# Connector.net
KiCad netlist of a schematic drawn in Altium Designer
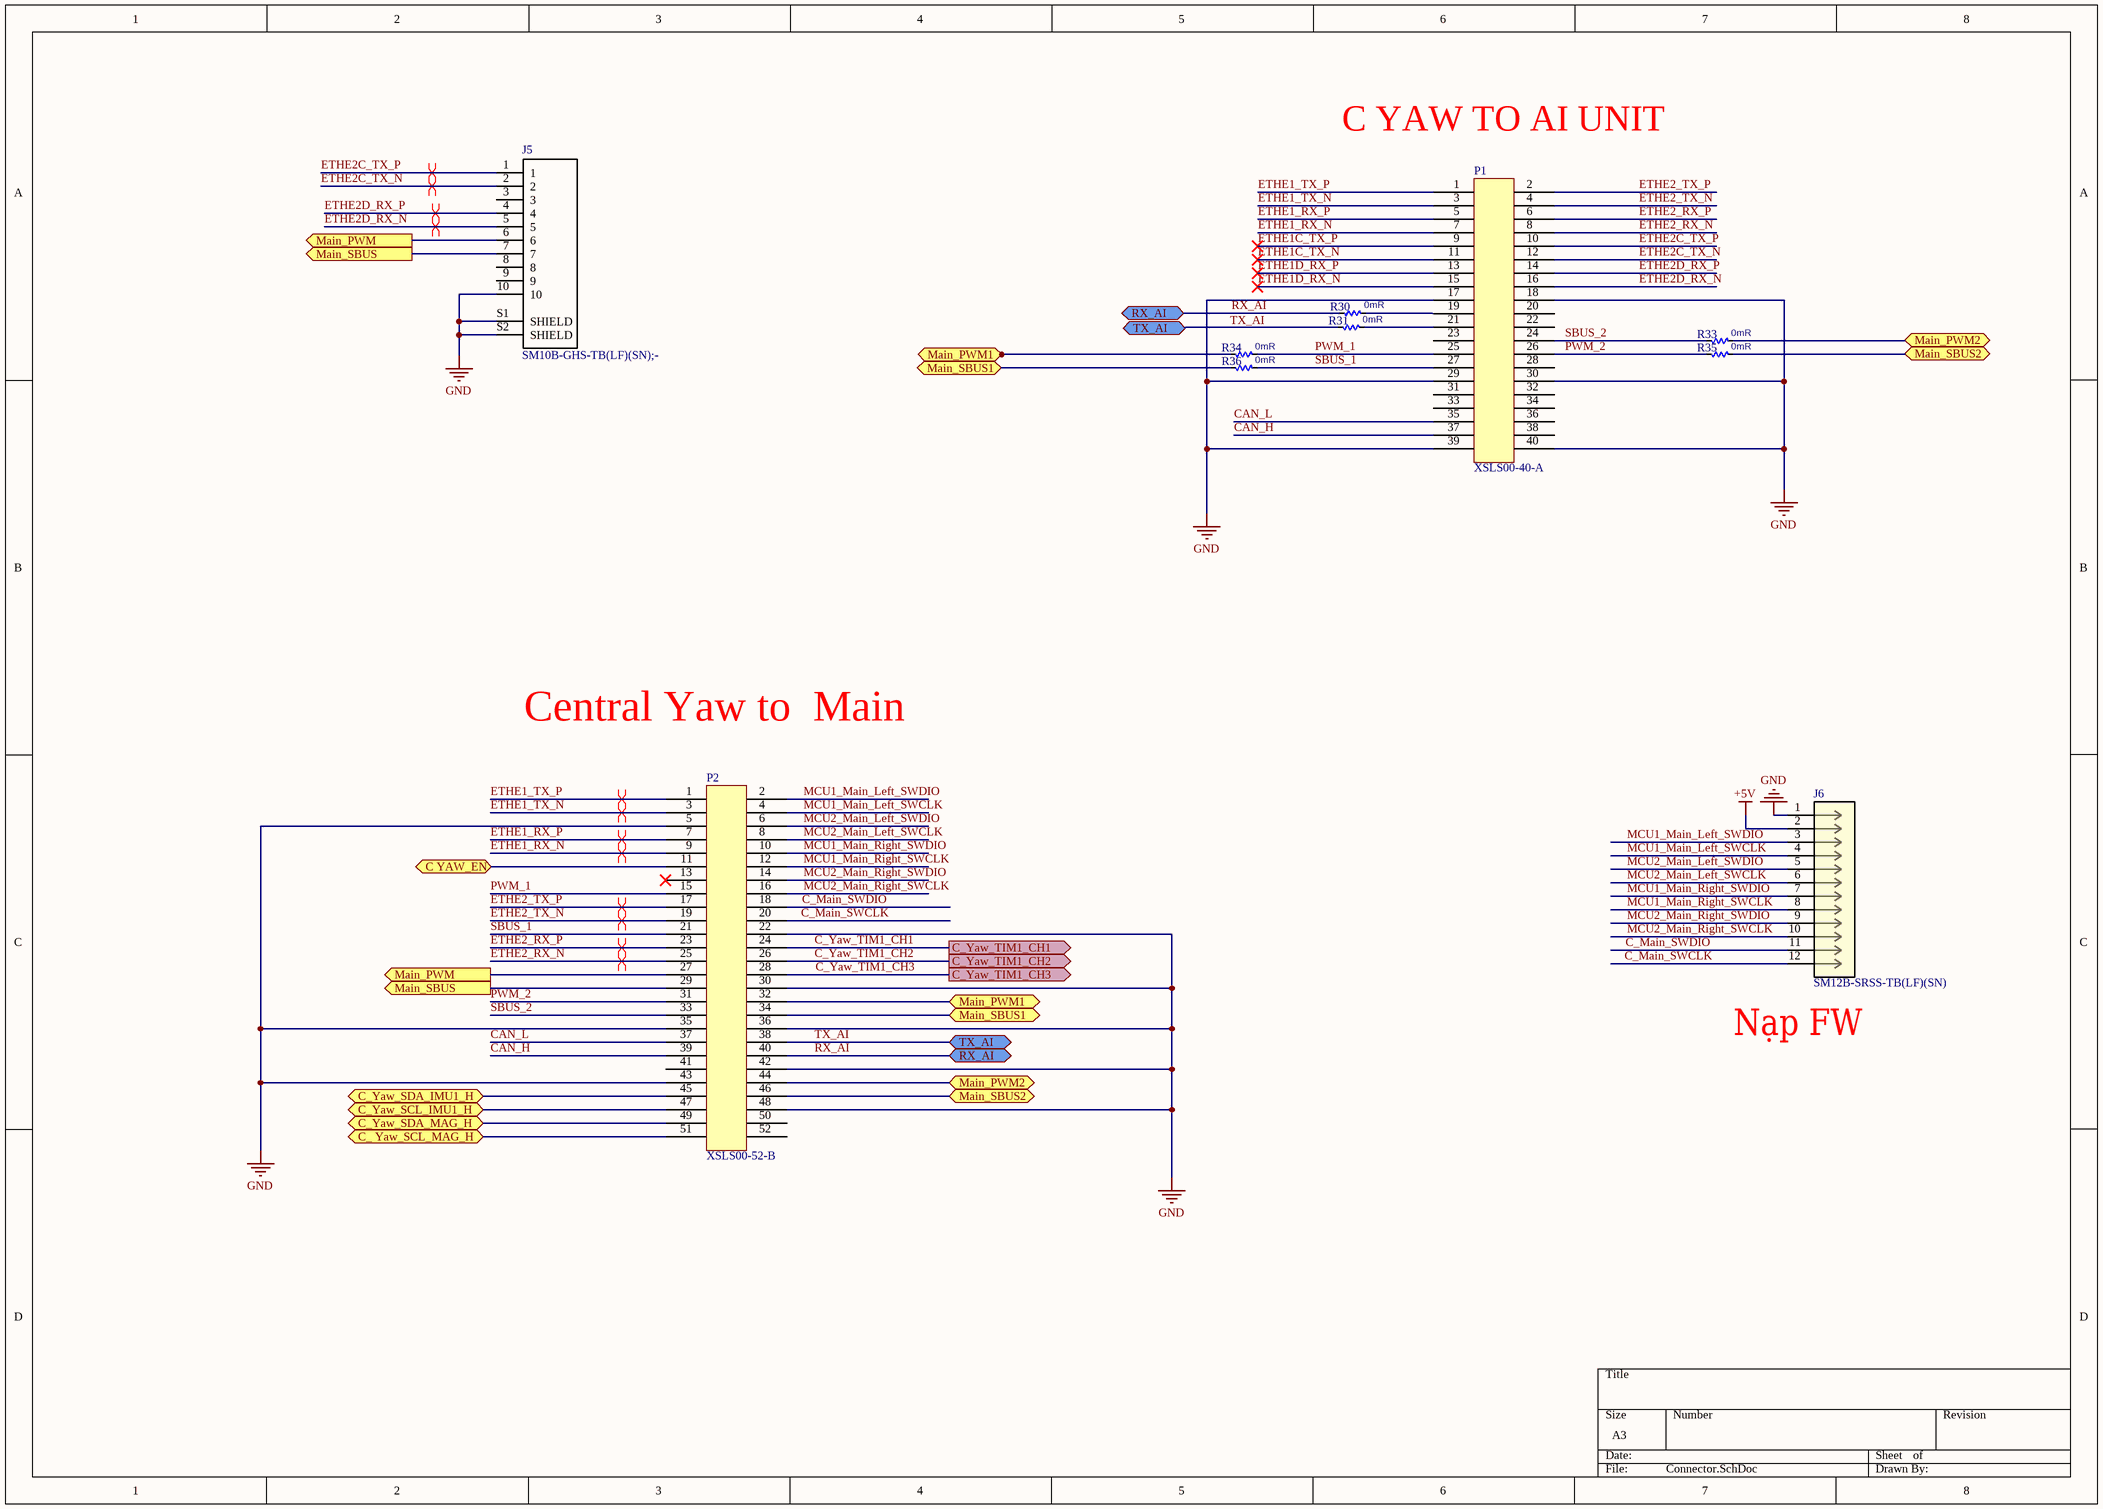
[diagram p0: Connector.SchDoc]

(export (version "E")
  (design (tool "Eeschema 10.0.6"))
  (components
    (comp (ref "J5")
      (value "SM10B-GHS-TB(LF)(SN);-")
      (footprint "SM10B-GHS-TB(LF)(SN)")
      (description "CONN HEADER GH SIDE 10POS 1.25MM")
      (fields (field (name "MANUFACTURER") "JST"))
      (libsource (lib "rtr") (part "SM10B-GHS-TB(LF)(SN);-"))
    )
    (comp (ref "J6")
      (value "SM12B-SRSS-TB(LF)(SN)")
      (footprint "CONN_SM12B-SRSS-TBLFSN_JST")
      (description "Description")
      (fields (field (name "COPYRIGHT") "Copyright (C) 2025 Ultra Librarian. All rights reserved."))
      (libsource (lib "RTR") (part "SM12B-SRSS-TBLFSN"))
    )
    (comp (ref "P1")
      (value "XSLS00-40-A")
      (footprint "XSXL40")
      (libsource (lib "Hera_Sight_PixyU2") (part "XSLS00-40-A"))
    )
    (comp (ref "P2")
      (value "XSLS00-52-B")
      (footprint "XSXL52")
      (libsource (lib "Hera_Sight_PixyU2") (part "XSLS00-52-B"))
    )
    (comp (ref "R30")
      (value "0mR")
      (footprint "RES0402")
      (description "RES 0402")
      (fields (field (name "MP") "add later") (field (name "Comment") "RES0402"))
      (libsource (lib "RTR") (part "RES0402"))
    )
    (comp (ref "R31")
      (value "0mR")
      (footprint "RES0402")
      (description "RES 0402")
      (fields (field (name "MP") "add later") (field (name "Comment") "RES0402"))
      (libsource (lib "RTR") (part "RES0402"))
    )
    (comp (ref "R33")
      (value "0mR")
      (footprint "RES0402")
      (description "RES 0402")
      (fields (field (name "MP") "add later") (field (name "Comment") "RES0402"))
      (libsource (lib "RTR") (part "RES0402"))
    )
    (comp (ref "R34")
      (value "0mR")
      (footprint "RES0402")
      (description "RES 0402")
      (fields (field (name "MP") "add later") (field (name "Comment") "RES0402"))
      (libsource (lib "RTR") (part "RES0402"))
    )
    (comp (ref "R35")
      (value "0mR")
      (footprint "RES0402")
      (description "RES 0402")
      (fields (field (name "MP") "add later") (field (name "Comment") "RES0402"))
      (libsource (lib "RTR") (part "RES0402"))
    )
    (comp (ref "R36")
      (value "0mR")
      (footprint "RES0402")
      (description "RES 0402")
      (fields (field (name "MP") "add later") (field (name "Comment") "RES0402"))
      (libsource (lib "RTR") (part "RES0402"))
    )
  )
  (nets
    (net (code "1") (name "+5V") (class "Default")
      (node (ref "J6") (pin "2") (pinfunction "2_2") (pintype "passive"))
    )
    (net (code "2") (name "/C YAW_EN") (class "Default") (node (ref "P2") (pin "11") (pintype "passive")))
    (net (code "3") (name "/CAN_H") (class "Default")
      (node (ref "P1") (pin "37") (pintype "passive"))
      (node (ref "P2") (pin "39") (pintype "passive"))
    )
    (net (code "4") (name "/CAN_L") (class "Default")
      (node (ref "P1") (pin "35") (pintype "passive"))
      (node (ref "P2") (pin "37") (pintype "passive"))
    )
    (net (code "5") (name "/C_ Yaw_SCL_MAG_H") (class "Default")
      (node (ref "P2") (pin "51") (pintype "passive"))
    )
    (net (code "6") (name "/C_Main_SWCLK") (class "Default")
      (node (ref "J6") (pin "12") (pinfunction "12_12") (pintype "passive"))
      (node (ref "P2") (pin "20") (pintype "passive"))
    )
    (net (code "7") (name "/C_Main_SWDIO") (class "Default")
      (node (ref "J6") (pin "11") (pinfunction "11_11") (pintype "passive"))
      (node (ref "P2") (pin "18") (pintype "passive"))
    )
    (net (code "8") (name "/C_Yaw_SCL_IMU1_H") (class "Default")
      (node (ref "P2") (pin "47") (pintype "passive"))
    )
    (net (code "9") (name "/C_Yaw_SDA_IMU1_H") (class "Default")
      (node (ref "P2") (pin "45") (pintype "passive"))
    )
    (net (code "10") (name "/C_Yaw_SDA_MAG_H") (class "Default")
      (node (ref "P2") (pin "49") (pintype "passive"))
    )
    (net (code "11") (name "/C_Yaw_TIM1_CH1") (class "Default")
      (node (ref "P2") (pin "24") (pintype "passive"))
    )
    (net (code "12") (name "/C_Yaw_TIM1_CH2") (class "Default")
      (node (ref "P2") (pin "26") (pintype "passive"))
    )
    (net (code "13") (name "/C_Yaw_TIM1_CH3") (class "Default")
      (node (ref "P2") (pin "28") (pintype "passive"))
    )
    (net (code "14") (name "/ETHE1C_TX_N") (class "Default")
      (node (ref "P1") (pin "11") (pintype "passive+no_connect"))
    )
    (net (code "15") (name "/ETHE1C_TX_P") (class "Default")
      (node (ref "P1") (pin "9") (pintype "passive+no_connect"))
    )
    (net (code "16") (name "/ETHE1D_RX_N") (class "Default")
      (node (ref "P1") (pin "15") (pintype "passive+no_connect"))
    )
    (net (code "17") (name "/ETHE1D_RX_P") (class "Default")
      (node (ref "P1") (pin "13") (pintype "passive+no_connect"))
    )
    (net (code "18") (name "/ETHE1_RX_N") (class "Default")
      (node (ref "P1") (pin "7") (pintype "passive"))
      (node (ref "P2") (pin "9") (pintype "passive"))
    )
    (net (code "19") (name "/ETHE1_RX_P") (class "Default")
      (node (ref "P1") (pin "5") (pintype "passive"))
      (node (ref "P2") (pin "7") (pintype "passive"))
    )
    (net (code "20") (name "/ETHE1_TX_N") (class "Default")
      (node (ref "P1") (pin "3") (pintype "passive"))
      (node (ref "P2") (pin "3") (pintype "passive"))
    )
    (net (code "21") (name "/ETHE1_TX_P") (class "Default")
      (node (ref "P1") (pin "1") (pintype "passive"))
      (node (ref "P2") (pin "1") (pintype "passive"))
    )
    (net (code "22") (name "/ETHE2C_TX_N") (class "Default")
      (node (ref "J5") (pin "2") (pinfunction "2_2") (pintype "passive"))
      (node (ref "P1") (pin "12") (pintype "passive"))
    )
    (net (code "23") (name "/ETHE2C_TX_P") (class "Default")
      (node (ref "J5") (pin "1") (pinfunction "1_1") (pintype "passive"))
      (node (ref "P1") (pin "10") (pintype "passive"))
    )
    (net (code "24") (name "/ETHE2D_RX_N") (class "Default")
      (node (ref "J5") (pin "5") (pinfunction "5_5") (pintype "passive"))
      (node (ref "P1") (pin "16") (pintype "passive"))
    )
    (net (code "25") (name "/ETHE2D_RX_P") (class "Default")
      (node (ref "J5") (pin "4") (pinfunction "4_4") (pintype "passive"))
      (node (ref "P1") (pin "14") (pintype "passive"))
    )
    (net (code "26") (name "/ETHE2_RX_N") (class "Default")
      (node (ref "P1") (pin "8") (pintype "passive"))
      (node (ref "P2") (pin "25") (pintype "passive"))
    )
    (net (code "27") (name "/ETHE2_RX_P") (class "Default")
      (node (ref "P1") (pin "6") (pintype "passive"))
      (node (ref "P2") (pin "23") (pintype "passive"))
    )
    (net (code "28") (name "/ETHE2_TX_N") (class "Default")
      (node (ref "P1") (pin "4") (pintype "passive"))
      (node (ref "P2") (pin "19") (pintype "passive"))
    )
    (net (code "29") (name "/ETHE2_TX_P") (class "Default")
      (node (ref "P1") (pin "2") (pintype "passive"))
      (node (ref "P2") (pin "17") (pintype "passive"))
    )
    (net (code "30") (name "/MCU1_Main_Left_SWCLK") (class "Default")
      (node (ref "J6") (pin "4") (pinfunction "4_4") (pintype "passive"))
      (node (ref "P2") (pin "4") (pintype "passive"))
    )
    (net (code "31") (name "/MCU1_Main_Left_SWDIO") (class "Default")
      (node (ref "J6") (pin "3") (pinfunction "3_3") (pintype "passive"))
      (node (ref "P2") (pin "2") (pintype "passive"))
    )
    (net (code "32") (name "/MCU1_Main_Right_SWCLK") (class "Default")
      (node (ref "J6") (pin "8") (pinfunction "8_8") (pintype "passive"))
      (node (ref "P2") (pin "12") (pintype "passive"))
    )
    (net (code "33") (name "/MCU1_Main_Right_SWDIO") (class "Default")
      (node (ref "J6") (pin "7") (pinfunction "7_7") (pintype "passive"))
      (node (ref "P2") (pin "10") (pintype "passive"))
    )
    (net (code "34") (name "/MCU2_Main_Left_SWCLK") (class "Default")
      (node (ref "J6") (pin "6") (pinfunction "6_6") (pintype "passive"))
      (node (ref "P2") (pin "8") (pintype "passive"))
    )
    (net (code "35") (name "/MCU2_Main_Left_SWDIO") (class "Default")
      (node (ref "J6") (pin "5") (pinfunction "5_5") (pintype "passive"))
      (node (ref "P2") (pin "6") (pintype "passive"))
    )
    (net (code "36") (name "/MCU2_Main_Right_SWCLK") (class "Default")
      (node (ref "J6") (pin "10") (pinfunction "10_10") (pintype "passive"))
      (node (ref "P2") (pin "16") (pintype "passive"))
    )
    (net (code "37") (name "/MCU2_Main_Right_SWDIO") (class "Default")
      (node (ref "J6") (pin "9") (pinfunction "9_9") (pintype "passive"))
      (node (ref "P2") (pin "14") (pintype "passive"))
    )
    (net (code "38") (name "/Main_PWM") (class "Default")
      (node (ref "J5") (pin "6") (pinfunction "6_6") (pintype "passive"))
      (node (ref "P2") (pin "27") (pintype "passive"))
    )
    (net (code "39") (name "/Main_PWM1") (class "Default")
      (node (ref "P2") (pin "32") (pintype "passive"))
      (node (ref "R34") (pin "1") (pinfunction "1_1") (pintype "passive"))
    )
    (net (code "40") (name "/Main_PWM2") (class "Default")
      (node (ref "P2") (pin "44") (pintype "passive"))
      (node (ref "R33") (pin "2") (pinfunction "2_2") (pintype "passive"))
    )
    (net (code "41") (name "/Main_SBUS") (class "Default")
      (node (ref "J5") (pin "7") (pinfunction "7_7") (pintype "passive"))
      (node (ref "P2") (pin "29") (pintype "passive"))
    )
    (net (code "42") (name "/Main_SBUS1") (class "Default")
      (node (ref "P2") (pin "34") (pintype "passive"))
      (node (ref "R36") (pin "1") (pinfunction "1_1") (pintype "passive"))
    )
    (net (code "43") (name "/Main_SBUS2") (class "Default")
      (node (ref "P2") (pin "46") (pintype "passive"))
      (node (ref "R35") (pin "2") (pinfunction "2_2") (pintype "passive"))
    )
    (net (code "44") (name "/PWM_1") (class "Default")
      (node (ref "P1") (pin "25") (pintype "passive"))
      (node (ref "P2") (pin "15") (pintype "passive"))
      (node (ref "R34") (pin "2") (pinfunction "2_2") (pintype "passive"))
    )
    (net (code "45") (name "/PWM_2") (class "Default")
      (node (ref "P1") (pin "26") (pintype "passive"))
      (node (ref "P2") (pin "31") (pintype "passive"))
      (node (ref "R35") (pin "1") (pinfunction "1_1") (pintype "passive"))
    )
    (net (code "46") (name "/RX_AI") (class "Default")
      (node (ref "P2") (pin "40") (pintype "passive"))
      (node (ref "R30") (pin "1") (pinfunction "1_1") (pintype "passive"))
    )
    (net (code "47") (name "/SBUS_1") (class "Default")
      (node (ref "P1") (pin "27") (pintype "passive"))
      (node (ref "P2") (pin "21") (pintype "passive"))
      (node (ref "R36") (pin "2") (pinfunction "2_2") (pintype "passive"))
    )
    (net (code "48") (name "/SBUS_2") (class "Default")
      (node (ref "P1") (pin "24") (pintype "passive"))
      (node (ref "P2") (pin "33") (pintype "passive"))
      (node (ref "R33") (pin "1") (pinfunction "1_1") (pintype "passive"))
    )
    (net (code "49") (name "/TX_AI") (class "Default")
      (node (ref "P2") (pin "38") (pintype "passive"))
      (node (ref "R31") (pin "1") (pinfunction "1_1") (pintype "passive"))
    )
    (net (code "50") (name "GND") (class "Default")
      (node (ref "J5") (pin "10") (pinfunction "10_10") (pintype "passive"))
      (node (ref "J5") (pin "S1") (pinfunction "SHIELD_S1") (pintype "passive"))
      (node (ref "J5") (pin "S2") (pinfunction "SHIELD_S2") (pintype "passive"))
      (node (ref "J6") (pin "1") (pinfunction "1_1") (pintype "passive"))
      (node (ref "P1") (pin "17") (pintype "passive"))
      (node (ref "P1") (pin "18") (pintype "passive"))
      (node (ref "P1") (pin "29") (pintype "passive"))
      (node (ref "P1") (pin "30") (pintype "passive"))
      (node (ref "P1") (pin "39") (pintype "passive"))
      (node (ref "P1") (pin "40") (pintype "passive"))
      (node (ref "P2") (pin "22") (pintype "passive"))
      (node (ref "P2") (pin "30") (pintype "passive"))
      (node (ref "P2") (pin "35") (pintype "passive"))
      (node (ref "P2") (pin "36") (pintype "passive"))
      (node (ref "P2") (pin "42") (pintype "passive"))
      (node (ref "P2") (pin "43") (pintype "passive"))
      (node (ref "P2") (pin "48") (pintype "passive"))
      (node (ref "P2") (pin "5") (pintype "passive"))
    )
    (net (code "51") (name "Net-(P1-Pad19)") (class "Default")
      (node (ref "P1") (pin "19") (pintype "passive"))
      (node (ref "R30") (pin "2") (pinfunction "2_2") (pintype "passive"))
    )
    (net (code "52") (name "Net-(P1-Pad21)") (class "Default")
      (node (ref "P1") (pin "21") (pintype "passive"))
      (node (ref "R31") (pin "2") (pinfunction "2_2") (pintype "passive"))
    )
    (net (code "53") (name "unconnected-(J5-Pad3)") (class "Default")
      (node (ref "J5") (pin "3") (pinfunction "3_3") (pintype "passive"))
    )
    (net (code "54") (name "unconnected-(J5-Pad8)") (class "Default")
      (node (ref "J5") (pin "8") (pinfunction "8_8") (pintype "passive"))
    )
    (net (code "55") (name "unconnected-(J5-Pad9)") (class "Default")
      (node (ref "J5") (pin "9") (pinfunction "9_9") (pintype "passive"))
    )
    (net (code "56") (name "unconnected-(P1-Pad20)") (class "Default")
      (node (ref "P1") (pin "20") (pintype "passive"))
    )
    (net (code "57") (name "unconnected-(P1-Pad22)") (class "Default")
      (node (ref "P1") (pin "22") (pintype "passive"))
    )
    (net (code "58") (name "unconnected-(P1-Pad23)") (class "Default")
      (node (ref "P1") (pin "23") (pintype "passive"))
    )
    (net (code "59") (name "unconnected-(P1-Pad28)") (class "Default")
      (node (ref "P1") (pin "28") (pintype "passive"))
    )
    (net (code "60") (name "unconnected-(P1-Pad31)") (class "Default")
      (node (ref "P1") (pin "31") (pintype "passive"))
    )
    (net (code "61") (name "unconnected-(P1-Pad32)") (class "Default")
      (node (ref "P1") (pin "32") (pintype "passive"))
    )
    (net (code "62") (name "unconnected-(P1-Pad33)") (class "Default")
      (node (ref "P1") (pin "33") (pintype "passive"))
    )
    (net (code "63") (name "unconnected-(P1-Pad34)") (class "Default")
      (node (ref "P1") (pin "34") (pintype "passive"))
    )
    (net (code "64") (name "unconnected-(P1-Pad36)") (class "Default")
      (node (ref "P1") (pin "36") (pintype "passive"))
    )
    (net (code "65") (name "unconnected-(P1-Pad38)") (class "Default")
      (node (ref "P1") (pin "38") (pintype "passive"))
    )
    (net (code "66") (name "unconnected-(P2-Pad13)") (class "Default")
      (node (ref "P2") (pin "13") (pintype "passive+no_connect"))
    )
    (net (code "67") (name "unconnected-(P2-Pad41)") (class "Default")
      (node (ref "P2") (pin "41") (pintype "passive"))
    )
    (net (code "68") (name "unconnected-(P2-Pad50)") (class "Default")
      (node (ref "P2") (pin "50") (pintype "passive"))
    )
    (net (code "69") (name "unconnected-(P2-Pad52)") (class "Default")
      (node (ref "P2") (pin "52") (pintype "passive"))
    )
  )
)
